# Untitled.net
KiCad netlist of a schematic drawn in EAGLE
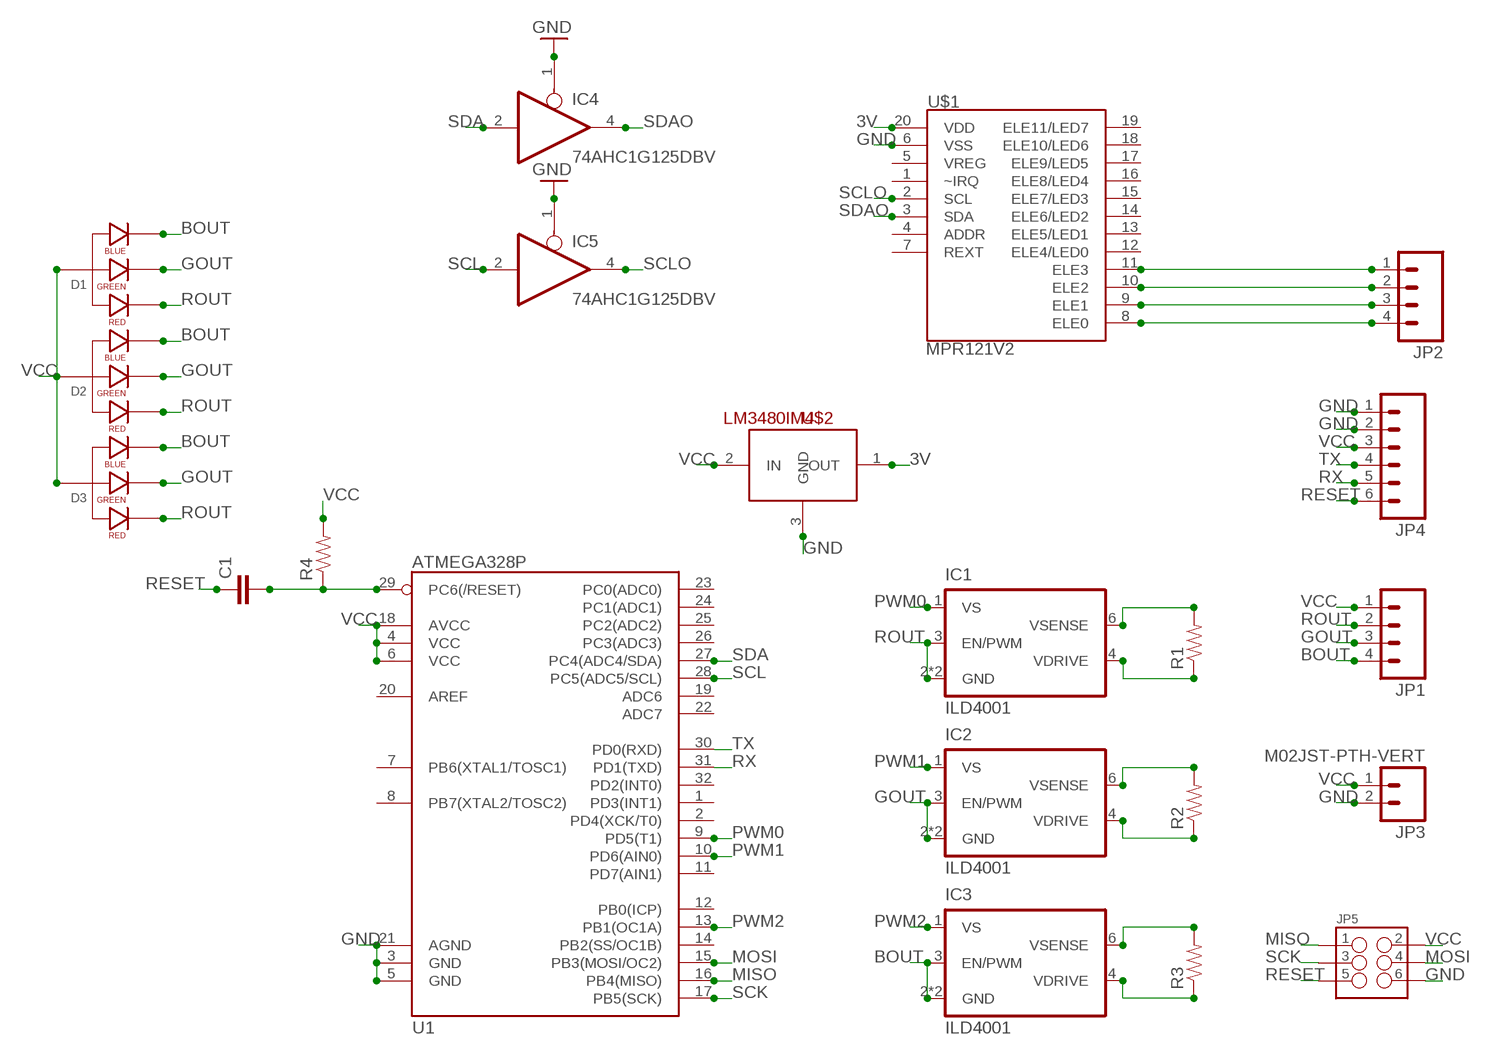
[diagram p0: schematic, sheet 1]

(export (version "E")
  (design (tool "Eeschema 10.0.6"))
  (components
    (comp (ref "C1")
      (value "CAP0805")
      (footprint "eagle-import:0805")
      (libsource (lib "eagle-import") (part "CAP0805"))
    )
    (comp (ref "D1")
      (value "LED-RGB-CA-THRUCLEAR")
      (footprint "eagle-import:LED-RGB-THRU")
      (libsource (lib "eagle-import") (part "LED-RGB-CA-THRUCLEAR"))
    )
    (comp (ref "D2")
      (value "LED-RGB-CA-THRUCLEAR")
      (footprint "eagle-import:LED-RGB-THRU")
      (libsource (lib "eagle-import") (part "LED-RGB-CA-THRUCLEAR"))
    )
    (comp (ref "D3")
      (value "LED-RGB-CA-THRUCLEAR")
      (footprint "eagle-import:LED-RGB-THRU")
      (libsource (lib "eagle-import") (part "LED-RGB-CA-THRUCLEAR"))
    )
    (comp (ref "IC1")
      (value "ILD4001")
      (footprint "eagle-import:SC74_INFINEON")
      (libsource (lib "eagle-import") (part "ILD4001"))
    )
    (comp (ref "IC2")
      (value "ILD4001")
      (footprint "eagle-import:SC74_INFINEON")
      (libsource (lib "eagle-import") (part "ILD4001"))
    )
    (comp (ref "IC3")
      (value "ILD4001")
      (footprint "eagle-import:SC74_INFINEON")
      (libsource (lib "eagle-import") (part "ILD4001"))
    )
    (comp (ref "IC4")
      (value "74AHC1G125DBV")
      (footprint "eagle-import:SOT23-5")
      (libsource (lib "eagle-import") (part "741G125DBVAHC"))
    )
    (comp (ref "IC5")
      (value "74AHC1G125DBV")
      (footprint "eagle-import:SOT23-5")
      (libsource (lib "eagle-import") (part "741G125DBVAHC"))
    )
    (comp (ref "JP1")
      (value "M04JST-PTH-VERT")
      (footprint "eagle-import:JST-4-PTH-VERT")
      (libsource (lib "eagle-import") (part "M04JST-PTH-VERT"))
    )
    (comp (ref "JP2")
      (value "M04JST-PTH-VERT")
      (footprint "eagle-import:JST-4-PTH-VERT")
      (libsource (lib "eagle-import") (part "M04JST-PTH-VERT"))
    )
    (comp (ref "JP3")
      (value "M02JST-PTH-VERT")
      (footprint "eagle-import:JST-2-PTH-VERT")
      (libsource (lib "eagle-import") (part "M02JST-PTH-VERT"))
    )
    (comp (ref "JP4")
      (value "M06LONGPADS")
      (footprint "eagle-import:1X06_LONGPADS")
      (libsource (lib "eagle-import") (part "M06LONGPADS"))
    )
    (comp (ref "JP5")
      (value "M03X22X3_SILK_MALE_PTH")
      (footprint "eagle-import:2X3")
      (libsource (lib "eagle-import") (part "M03X22X3_SILK_MALE_PTH"))
    )
    (comp (ref "R1")
      (value "RESISTOR0805-RES")
      (footprint "eagle-import:0805")
      (libsource (lib "eagle-import") (part "RESISTOR0805-RES"))
    )
    (comp (ref "R2")
      (value "RESISTOR0805-RES")
      (footprint "eagle-import:0805")
      (libsource (lib "eagle-import") (part "RESISTOR0805-RES"))
    )
    (comp (ref "R3")
      (value "RESISTOR0805-RES")
      (footprint "eagle-import:0805")
      (libsource (lib "eagle-import") (part "RESISTOR0805-RES"))
    )
    (comp (ref "R4")
      (value "RESISTOR0805-RES")
      (footprint "eagle-import:0805")
      (libsource (lib "eagle-import") (part "RESISTOR0805-RES"))
    )
    (comp (ref "U$1")
      (value "MPR121V2")
      (footprint "eagle-import:QFN-20-0.4MM-V2")
      (libsource (lib "eagle-import") (part "MPR121V2"))
    )
    (comp (ref "U$2")
      (value "LM3480IM4")
      (footprint "eagle-import:SOT23-3")
      (libsource (lib "eagle-import") (part "LM3480IM4"))
    )
    (comp (ref "U1")
      (value "ATMEGA328P")
      (footprint "eagle-import:TQFP32-08")
      (libsource (lib "eagle-import") (part "ATMEGA328_SMT"))
    )
  )
  (nets
    (net (code "1") (name "/3V") (class "Default")
      (node (ref "U$1") (pin "20") (pinfunction "VDD_20") (pintype "bidirectional"))
      (node (ref "U$2") (pin "1") (pinfunction "OUT_1") (pintype "bidirectional"))
    )
    (net (code "2") (name "/BOUT") (class "Default")
      (node (ref "D1") (pin "4") (pinfunction "BLUE_CATHODE_4") (pintype "bidirectional"))
      (node (ref "D2") (pin "4") (pinfunction "BLUE_CATHODE_4") (pintype "bidirectional"))
      (node (ref "D3") (pin "4") (pinfunction "BLUE_CATHODE_4") (pintype "bidirectional"))
      (node (ref "IC3") (pin "2") (pinfunction "GND_2") (pintype "power_in"))
      (node (ref "IC3") (pin "3") (pinfunction "EN/PWM_3") (pintype "input"))
      (node (ref "IC3") (pin "5") (pinfunction "GND_5") (pintype "power_in"))
      (node (ref "JP1") (pin "4") (pinfunction "4_4") (pintype "passive"))
    )
    (net (code "3") (name "/GOUT") (class "Default")
      (node (ref "D1") (pin "3") (pinfunction "GREEN_CATHODE_3") (pintype "bidirectional"))
      (node (ref "D2") (pin "3") (pinfunction "GREEN_CATHODE_3") (pintype "bidirectional"))
      (node (ref "D3") (pin "3") (pinfunction "GREEN_CATHODE_3") (pintype "bidirectional"))
      (node (ref "IC2") (pin "2") (pinfunction "GND_2") (pintype "power_in"))
      (node (ref "IC2") (pin "3") (pinfunction "EN/PWM_3") (pintype "input"))
      (node (ref "IC2") (pin "5") (pinfunction "GND_5") (pintype "power_in"))
      (node (ref "JP1") (pin "3") (pinfunction "3_3") (pintype "passive"))
    )
    (net (code "4") (name "/MISO") (class "Default")
      (node (ref "JP5") (pin "1") (pinfunction "1_1") (pintype "bidirectional"))
      (node (ref "U1") (pin "16") (pinfunction "PB4(MISO)_16") (pintype "bidirectional"))
    )
    (net (code "5") (name "/MOSI") (class "Default")
      (node (ref "JP5") (pin "4") (pinfunction "4_4") (pintype "bidirectional"))
      (node (ref "U1") (pin "15") (pinfunction "PB3(MOSI/OC2)_15") (pintype "bidirectional"))
    )
    (net (code "6") (name "/PWM0") (class "Default")
      (node (ref "IC1") (pin "1") (pinfunction "VS_1") (pintype "input"))
      (node (ref "U1") (pin "9") (pinfunction "PD5(T1)_9") (pintype "bidirectional"))
    )
    (net (code "7") (name "/PWM1") (class "Default")
      (node (ref "IC2") (pin "1") (pinfunction "VS_1") (pintype "input"))
      (node (ref "U1") (pin "10") (pinfunction "PD6(AIN0)_10") (pintype "bidirectional"))
    )
    (net (code "8") (name "/PWM2") (class "Default")
      (node (ref "IC3") (pin "1") (pinfunction "VS_1") (pintype "input"))
      (node (ref "U1") (pin "13") (pinfunction "PB1(OC1A)_13") (pintype "bidirectional"))
    )
    (net (code "9") (name "/RESET") (class "Default")
      (node (ref "C1") (pin "1") (pinfunction "1_1") (pintype "passive"))
      (node (ref "JP4") (pin "6") (pinfunction "6_6") (pintype "passive"))
      (node (ref "JP5") (pin "5") (pinfunction "5_5") (pintype "bidirectional"))
    )
    (net (code "10") (name "/ROUT") (class "Default")
      (node (ref "D1") (pin "1") (pinfunction "RED_CATHODE_1") (pintype "bidirectional"))
      (node (ref "D2") (pin "1") (pinfunction "RED_CATHODE_1") (pintype "bidirectional"))
      (node (ref "D3") (pin "1") (pinfunction "RED_CATHODE_1") (pintype "bidirectional"))
      (node (ref "IC1") (pin "2") (pinfunction "GND_2") (pintype "power_in"))
      (node (ref "IC1") (pin "3") (pinfunction "EN/PWM_3") (pintype "input"))
      (node (ref "IC1") (pin "5") (pinfunction "GND_5") (pintype "power_in"))
      (node (ref "JP1") (pin "2") (pinfunction "2_2") (pintype "passive"))
    )
    (net (code "11") (name "/RX") (class "Default")
      (node (ref "JP4") (pin "5") (pinfunction "5_5") (pintype "passive"))
      (node (ref "U1") (pin "31") (pinfunction "PD1(TXD)_31") (pintype "bidirectional"))
    )
    (net (code "12") (name "/SCK") (class "Default")
      (node (ref "JP5") (pin "3") (pinfunction "3_3") (pintype "bidirectional"))
      (node (ref "U1") (pin "17") (pinfunction "PB5(SCK)_17") (pintype "bidirectional"))
    )
    (net (code "13") (name "/SCL") (class "Default")
      (node (ref "IC5") (pin "2") (pinfunction "I_2") (pintype "input"))
      (node (ref "U1") (pin "28") (pinfunction "PC5(ADC5/SCL)_28") (pintype "bidirectional"))
    )
    (net (code "14") (name "/SCLO") (class "Default")
      (node (ref "IC5") (pin "4") (pinfunction "O_4") (pintype "tri_state"))
      (node (ref "U$1") (pin "2") (pinfunction "SCL_2") (pintype "bidirectional"))
    )
    (net (code "15") (name "/SDA") (class "Default")
      (node (ref "IC4") (pin "2") (pinfunction "I_2") (pintype "input"))
      (node (ref "U1") (pin "27") (pinfunction "PC4(ADC4/SDA)_27") (pintype "bidirectional"))
    )
    (net (code "16") (name "/SDAO") (class "Default")
      (node (ref "IC4") (pin "4") (pinfunction "O_4") (pintype "tri_state"))
      (node (ref "U$1") (pin "3") (pinfunction "SDA_3") (pintype "bidirectional"))
    )
    (net (code "17") (name "/TX") (class "Default")
      (node (ref "JP4") (pin "4") (pinfunction "4_4") (pintype "passive"))
      (node (ref "U1") (pin "30") (pinfunction "PD0(RXD)_30") (pintype "bidirectional"))
    )
    (net (code "18") (name "/VCC") (class "Default")
      (node (ref "D1") (pin "2") (pinfunction "ANODE_2") (pintype "bidirectional"))
      (node (ref "D2") (pin "2") (pinfunction "ANODE_2") (pintype "bidirectional"))
      (node (ref "D3") (pin "2") (pinfunction "ANODE_2") (pintype "bidirectional"))
      (node (ref "JP1") (pin "1") (pinfunction "1_1") (pintype "passive"))
      (node (ref "JP3") (pin "1") (pinfunction "1_1") (pintype "passive"))
      (node (ref "JP4") (pin "3") (pinfunction "3_3") (pintype "passive"))
      (node (ref "JP5") (pin "2") (pinfunction "2_2") (pintype "bidirectional"))
      (node (ref "R4") (pin "2") (pinfunction "2_2") (pintype "passive"))
      (node (ref "U$2") (pin "2") (pinfunction "IN_2") (pintype "bidirectional"))
      (node (ref "U1") (pin "18") (pinfunction "AVCC_18") (pintype "bidirectional"))
      (node (ref "U1") (pin "4") (pinfunction "VCC_4") (pintype "bidirectional"))
      (node (ref "U1") (pin "6") (pinfunction "VCC_6") (pintype "bidirectional"))
    )
    (net (code "19") (name "GND") (class "Default")
      (node (ref "IC4") (pin "1") (pinfunction "OE_1") (pintype "input"))
      (node (ref "IC5") (pin "1") (pinfunction "OE_1") (pintype "input"))
      (node (ref "JP3") (pin "2") (pinfunction "2_2") (pintype "passive"))
      (node (ref "JP4") (pin "1") (pinfunction "1_1") (pintype "passive"))
      (node (ref "JP4") (pin "2") (pinfunction "2_2") (pintype "passive"))
      (node (ref "JP5") (pin "6") (pinfunction "6_6") (pintype "bidirectional"))
      (node (ref "U$1") (pin "6") (pinfunction "VSS_6") (pintype "bidirectional"))
      (node (ref "U$2") (pin "3") (pinfunction "GND_3") (pintype "bidirectional"))
      (node (ref "U1") (pin "21") (pinfunction "AGND_21") (pintype "bidirectional"))
      (node (ref "U1") (pin "3") (pinfunction "GND_3") (pintype "bidirectional"))
      (node (ref "U1") (pin "5") (pinfunction "GND_5") (pintype "bidirectional"))
    )
    (net (code "20") (name "Net-(IC1-VDRIVE)") (class "Default")
      (node (ref "IC1") (pin "4") (pinfunction "VDRIVE_4") (pintype "output"))
      (node (ref "R1") (pin "1") (pinfunction "1_1") (pintype "passive"))
    )
    (net (code "21") (name "Net-(IC1-VSENSE)") (class "Default")
      (node (ref "IC1") (pin "6") (pinfunction "VSENSE_6") (pintype "input"))
      (node (ref "R1") (pin "2") (pinfunction "2_2") (pintype "passive"))
    )
    (net (code "22") (name "Net-(IC2-VDRIVE)") (class "Default")
      (node (ref "IC2") (pin "4") (pinfunction "VDRIVE_4") (pintype "output"))
      (node (ref "R2") (pin "1") (pinfunction "1_1") (pintype "passive"))
    )
    (net (code "23") (name "Net-(IC2-VSENSE)") (class "Default")
      (node (ref "IC2") (pin "6") (pinfunction "VSENSE_6") (pintype "input"))
      (node (ref "R2") (pin "2") (pinfunction "2_2") (pintype "passive"))
    )
    (net (code "24") (name "Net-(IC3-VDRIVE)") (class "Default")
      (node (ref "IC3") (pin "4") (pinfunction "VDRIVE_4") (pintype "output"))
      (node (ref "R3") (pin "1") (pinfunction "1_1") (pintype "passive"))
    )
    (net (code "25") (name "Net-(IC3-VSENSE)") (class "Default")
      (node (ref "IC3") (pin "6") (pinfunction "VSENSE_6") (pintype "input"))
      (node (ref "R3") (pin "2") (pinfunction "2_2") (pintype "passive"))
    )
    (net (code "26") (name "Net-(U$1-ELE0)") (class "Default")
      (node (ref "JP2") (pin "4") (pinfunction "4_4") (pintype "passive"))
      (node (ref "U$1") (pin "8") (pinfunction "ELE0_8") (pintype "bidirectional"))
    )
    (net (code "27") (name "Net-(U$1-ELE1)") (class "Default")
      (node (ref "JP2") (pin "3") (pinfunction "3_3") (pintype "passive"))
      (node (ref "U$1") (pin "9") (pinfunction "ELE1_9") (pintype "bidirectional"))
    )
    (net (code "28") (name "Net-(U$1-ELE2)") (class "Default")
      (node (ref "JP2") (pin "2") (pinfunction "2_2") (pintype "passive"))
      (node (ref "U$1") (pin "10") (pinfunction "ELE2_10") (pintype "bidirectional"))
    )
    (net (code "29") (name "Net-(U$1-ELE3)") (class "Default")
      (node (ref "JP2") (pin "1") (pinfunction "1_1") (pintype "passive"))
      (node (ref "U$1") (pin "11") (pinfunction "ELE3_11") (pintype "bidirectional"))
    )
    (net (code "30") (name "Net-(U1-PC6({slash}RESET))") (class "Default")
      (node (ref "C1") (pin "2") (pinfunction "2_2") (pintype "passive"))
      (node (ref "R4") (pin "1") (pinfunction "1_1") (pintype "passive"))
      (node (ref "U1") (pin "29") (pinfunction "PC6(/RESET)_29") (pintype "bidirectional"))
    )
    (net (code "31") (name "unconnected-(U$1-ADDR-Pad4)") (class "Default")
      (node (ref "U$1") (pin "4") (pinfunction "ADDR_4") (pintype "bidirectional"))
    )
    (net (code "32") (name "unconnected-(U$1-ELE4{slash}LED0-Pad12)") (class "Default")
      (node (ref "U$1") (pin "12") (pinfunction "ELE4/LED0_12") (pintype "bidirectional"))
    )
    (net (code "33") (name "unconnected-(U$1-ELE5{slash}LED1-Pad13)") (class "Default")
      (node (ref "U$1") (pin "13") (pinfunction "ELE5/LED1_13") (pintype "bidirectional"))
    )
    (net (code "34") (name "unconnected-(U$1-ELE6{slash}LED2-Pad14)") (class "Default")
      (node (ref "U$1") (pin "14") (pinfunction "ELE6/LED2_14") (pintype "bidirectional"))
    )
    (net (code "35") (name "unconnected-(U$1-ELE7{slash}LED3-Pad15)") (class "Default")
      (node (ref "U$1") (pin "15") (pinfunction "ELE7/LED3_15") (pintype "bidirectional"))
    )
    (net (code "36") (name "unconnected-(U$1-ELE8{slash}LED4-Pad16)") (class "Default")
      (node (ref "U$1") (pin "16") (pinfunction "ELE8/LED4_16") (pintype "bidirectional"))
    )
    (net (code "37") (name "unconnected-(U$1-ELE9{slash}LED5-Pad17)") (class "Default")
      (node (ref "U$1") (pin "17") (pinfunction "ELE9/LED5_17") (pintype "bidirectional"))
    )
    (net (code "38") (name "unconnected-(U$1-ELE10{slash}LED6-Pad18)") (class "Default")
      (node (ref "U$1") (pin "18") (pinfunction "ELE10/LED6_18") (pintype "bidirectional"))
    )
    (net (code "39") (name "unconnected-(U$1-ELE11{slash}LED7-Pad19)") (class "Default")
      (node (ref "U$1") (pin "19") (pinfunction "ELE11/LED7_19") (pintype "bidirectional"))
    )
    (net (code "40") (name "unconnected-(U$1-REXT-Pad7)") (class "Default")
      (node (ref "U$1") (pin "7") (pinfunction "REXT_7") (pintype "bidirectional"))
    )
    (net (code "41") (name "unconnected-(U$1-VREG-Pad5)") (class "Default")
      (node (ref "U$1") (pin "5") (pinfunction "VREG_5") (pintype "bidirectional"))
    )
    (net (code "42") (name "unconnected-(U$1-~{IRQ}-Pad1)") (class "Default")
      (node (ref "U$1") (pin "1") (pinfunction "~{IRQ}_1") (pintype "bidirectional"))
    )
    (net (code "43") (name "unconnected-(U1-ADC6-Pad19)") (class "Default")
      (node (ref "U1") (pin "19") (pinfunction "ADC6_19") (pintype "bidirectional"))
    )
    (net (code "44") (name "unconnected-(U1-ADC7-Pad22)") (class "Default")
      (node (ref "U1") (pin "22") (pinfunction "ADC7_22") (pintype "bidirectional"))
    )
    (net (code "45") (name "unconnected-(U1-AREF-Pad20)") (class "Default")
      (node (ref "U1") (pin "20") (pinfunction "AREF_20") (pintype "bidirectional"))
    )
    (net (code "46") (name "unconnected-(U1-PB0(ICP)-Pad12)") (class "Default")
      (node (ref "U1") (pin "12") (pinfunction "PB0(ICP)_12") (pintype "bidirectional"))
    )
    (net (code "47") (name "unconnected-(U1-PB2(SS{slash}OC1B)-Pad14)") (class "Default")
      (node (ref "U1") (pin "14") (pinfunction "PB2(SS/OC1B)_14") (pintype "bidirectional"))
    )
    (net (code "48") (name "unconnected-(U1-PB6(XTAL1{slash}TOSC1)-Pad7)") (class "Default")
      (node (ref "U1") (pin "7") (pinfunction "PB6(XTAL1/TOSC1)_7") (pintype "bidirectional"))
    )
    (net (code "49") (name "unconnected-(U1-PB7(XTAL2{slash}TOSC2)-Pad8)") (class "Default")
      (node (ref "U1") (pin "8") (pinfunction "PB7(XTAL2/TOSC2)_8") (pintype "bidirectional"))
    )
    (net (code "50") (name "unconnected-(U1-PC0(ADC0)-Pad23)") (class "Default")
      (node (ref "U1") (pin "23") (pinfunction "PC0(ADC0)_23") (pintype "bidirectional"))
    )
    (net (code "51") (name "unconnected-(U1-PC1(ADC1)-Pad24)") (class "Default")
      (node (ref "U1") (pin "24") (pinfunction "PC1(ADC1)_24") (pintype "bidirectional"))
    )
    (net (code "52") (name "unconnected-(U1-PC2(ADC2)-Pad25)") (class "Default")
      (node (ref "U1") (pin "25") (pinfunction "PC2(ADC2)_25") (pintype "bidirectional"))
    )
    (net (code "53") (name "unconnected-(U1-PC3(ADC3)-Pad26)") (class "Default")
      (node (ref "U1") (pin "26") (pinfunction "PC3(ADC3)_26") (pintype "bidirectional"))
    )
    (net (code "54") (name "unconnected-(U1-PD2(INT0)-Pad32)") (class "Default")
      (node (ref "U1") (pin "32") (pinfunction "PD2(INT0)_32") (pintype "bidirectional"))
    )
    (net (code "55") (name "unconnected-(U1-PD3(INT1)-Pad1)") (class "Default")
      (node (ref "U1") (pin "1") (pinfunction "PD3(INT1)_1") (pintype "bidirectional"))
    )
    (net (code "56") (name "unconnected-(U1-PD4(XCK{slash}T0)-Pad2)") (class "Default")
      (node (ref "U1") (pin "2") (pinfunction "PD4(XCK/T0)_2") (pintype "bidirectional"))
    )
    (net (code "57") (name "unconnected-(U1-PD7(AIN1)-Pad11)") (class "Default")
      (node (ref "U1") (pin "11") (pinfunction "PD7(AIN1)_11") (pintype "bidirectional"))
    )
  )
)
